# IHM.net
KiCad netlist of a schematic drawn in Altium Designer
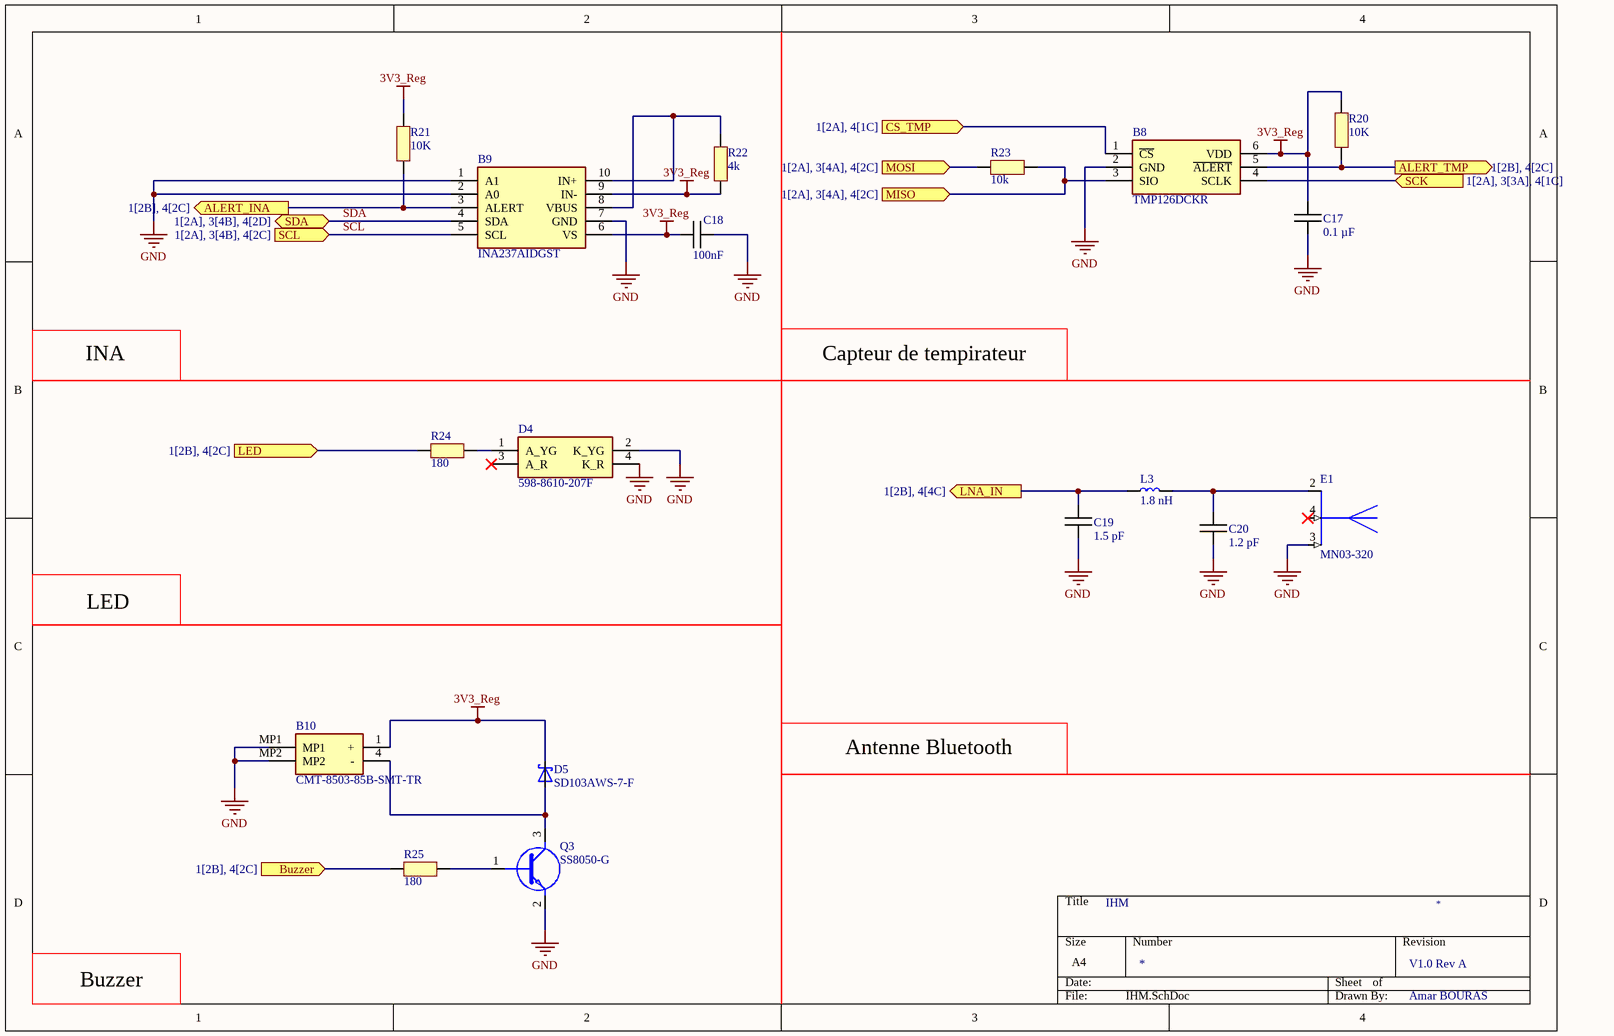
[diagram p0: IHM.SchDoc]

(export (version "E")
  (design (tool "Eeschema 10.0.6"))
  (components
    (comp (ref "B8")
      (value "TMP126DCKR")
      (footprint "SOT65P210X110-6N")
      (fields (field (name "MOUSER PART NUMBER") "595-TMP126DCKR"))
      (libsource (lib "SCHLibrary") (part "TMP126DCKR"))
    )
    (comp (ref "B9")
      (value "INA237AIDGST")
      (footprint "SOP50P490X110-10N")
      (fields (field (name "MOUSER PART NUMBER") "595-INA237AIDGST"))
      (libsource (lib "SCHLibrary") (part "INA237AIDGST"))
    )
    (comp (ref "B10")
      (value "CMT-8503-85B-SMT-TR")
      (footprint "CMT850385BSMTTR")
      (fields (field (name "MOUSER PART NUMBER") "490-CMT-850385BSMTTR"))
      (libsource (lib "SCHLibrary") (part "CMT-8503-85B-SMT-TR"))
    )
    (comp (ref "C17")
      (value "0.1 µF")
      (footprint "CAPC1005X06N")
      (libsource (lib "SCHLibrary") (part "Capacitor"))
    )
    (comp (ref "C18")
      (value "100nF")
      (footprint "CAPC1005X06N")
      (libsource (lib "SCHLibrary") (part "Capacitor"))
    )
    (comp (ref "C19")
      (value "1.5 pF")
      (footprint "CAPC1005X06N")
      (libsource (lib "SCHLibrary") (part "Capacitor"))
    )
    (comp (ref "C20")
      (value "1.2 pF")
      (footprint "CAPC1005X06N")
      (libsource (lib "SCHLibrary") (part "Capacitor"))
    )
    (comp (ref "D4")
      (value "598-8610-207F")
      (footprint "5988610207F")
      (description "Standard LEDs - SMD Red/Green WC 80/50mcd 645/570nm")
      (fields (field (name "MOUSER PART NUMBER") "645-598-8610-207F"))
      (libsource (lib "SCHLibrary") (part "598-8610-207F"))
    )
    (comp (ref "D5")
      (value "SD103AWS-7-F")
      (footprint "SD103AWS-7-F")
      (description "Diode Array 3 Independent Schottky 40V 175mA Surface Mount 6-TSSOP, SC-88, SOT-363")
      (libsource (lib "SCHLibrary") (part "SD103AWS-7-F"))
    )
    (comp (ref "E1")
      (value "MN03-320")
      (footprint "XCVR_NN03-320")
      (fields
        (field (name "MANUFACTURER_PART_NUMBER") "NN03-320")
        (field (name "MOUSER PART NUMBER") "128-NN03-320")
      )
      (libsource (lib "SCHLibrary") (part "NN03-320"))
    )
    (comp (ref "L3")
      (value "1.8 nH")
      (footprint "LQPC1005X06N")
      (libsource (lib "SCHLibrary") (part "Bobine"))
    )
    (comp (ref "Q3")
      (value "SS8050-G")
      (footprint "SS8050-G")
      (description "Bipolar Transistors - BJT NPN TRANSISTOR 1.5A 40V")
      (libsource (lib "SCHLibrary") (part "SS8050-G"))
    )
    (comp (ref "R20") (value "10K") (footprint "RESC1005X06N") (libsource (lib "") (part "Resistor_1")))
    (comp (ref "R21") (value "10K") (footprint "RESC1005X06N") (libsource (lib "") (part "Resistor_1")))
    (comp (ref "R22") (value "4k") (footprint "RESC1005X06N") (libsource (lib "") (part "Resistor_1")))
    (comp (ref "R23")
      (value "10k")
      (footprint "RESC1005X06N")
      (libsource (lib "SCHLibrary") (part "Resistor"))
    )
    (comp (ref "R24")
      (value "180")
      (footprint "RESC1005X06N")
      (libsource (lib "SCHLibrary") (part "Resistor"))
    )
    (comp (ref "R25")
      (value "180")
      (footprint "RESC1005X06N")
      (libsource (lib "SCHLibrary") (part "Resistor"))
    )
  )
  (nets
    (net (code "1") (name "/ALERT_INA") (class "Default")
      (node (ref "B9") (pin "3") (pinfunction "ALERT_3") (pintype "passive"))
      (node (ref "R21") (pin "1") (pinfunction "1_1") (pintype "passive"))
    )
    (net (code "2") (name "/ALERT_TMP") (class "Default")
      (node (ref "B8") (pin "5") (pinfunction "~{ALERT}_5") (pintype "passive"))
      (node (ref "R20") (pin "1") (pinfunction "1_1") (pintype "passive"))
    )
    (net (code "3") (name "/Buzzer") (class "Default")
      (node (ref "R25") (pin "2") (pinfunction "2_2") (pintype "passive"))
    )
    (net (code "4") (name "/CS_TMP") (class "Default")
      (node (ref "B8") (pin "1") (pinfunction "~{CS}_1") (pintype "passive"))
    )
    (net (code "5") (name "/LED") (class "Default")
      (node (ref "R24") (pin "2") (pinfunction "2_2") (pintype "passive"))
    )
    (net (code "6") (name "/LNA_IN") (class "Default")
      (node (ref "C19") (pin "2") (pinfunction "2_2") (pintype "passive"))
      (node (ref "L3") (pin "1") (pinfunction "1_1") (pintype "passive"))
    )
    (net (code "7") (name "/MISO") (class "Default")
      (node (ref "B8") (pin "3") (pinfunction "SIO_3") (pintype "passive"))
      (node (ref "R23") (pin "1") (pinfunction "1_1") (pintype "passive"))
    )
    (net (code "8") (name "/MOSI") (class "Default")
      (node (ref "R23") (pin "2") (pinfunction "2_2") (pintype "passive"))
    )
    (net (code "9") (name "/SCK") (class "Default")
      (node (ref "B8") (pin "4") (pinfunction "SCLK_4") (pintype "passive"))
    )
    (net (code "10") (name "/SCL") (class "Default")
      (node (ref "B9") (pin "5") (pinfunction "SCL_5") (pintype "passive"))
    )
    (net (code "11") (name "/SDA") (class "Default")
      (node (ref "B9") (pin "4") (pinfunction "SDA_4") (pintype "passive"))
    )
    (net (code "12") (name "3V3_Reg") (class "Default")
      (node (ref "B10") (pin "1") (pinfunction "+_1") (pintype "passive"))
      (node (ref "B8") (pin "6") (pinfunction "VDD_6") (pintype "passive"))
      (node (ref "B9") (pin "6") (pinfunction "VS_6") (pintype "passive"))
      (node (ref "B9") (pin "9") (pinfunction "IN-_9") (pintype "passive"))
      (node (ref "C17") (pin "2") (pinfunction "2_2") (pintype "passive"))
      (node (ref "C18") (pin "1") (pinfunction "1_1") (pintype "passive"))
      (node (ref "D5") (pin "1") (pinfunction "C_1") (pintype "passive"))
      (node (ref "R20") (pin "2") (pinfunction "2_2") (pintype "passive"))
      (node (ref "R21") (pin "2") (pinfunction "2_2") (pintype "passive"))
      (node (ref "R22") (pin "1") (pinfunction "1_1") (pintype "passive"))
    )
    (net (code "13") (name "GND") (class "Default")
      (node (ref "B10") (pin "MP1") (pinfunction "MP1_MP1") (pintype "passive"))
      (node (ref "B10") (pin "MP2") (pinfunction "MP2_MP2") (pintype "passive"))
      (node (ref "B8") (pin "2") (pinfunction "GND_2") (pintype "passive"))
      (node (ref "B9") (pin "1") (pinfunction "A1_1") (pintype "passive"))
      (node (ref "B9") (pin "2") (pinfunction "A0_2") (pintype "passive"))
      (node (ref "B9") (pin "7") (pinfunction "GND_7") (pintype "passive"))
      (node (ref "C17") (pin "1") (pinfunction "1_1") (pintype "passive"))
      (node (ref "C18") (pin "2") (pinfunction "2_2") (pintype "passive"))
      (node (ref "C19") (pin "1") (pinfunction "1_1") (pintype "passive"))
      (node (ref "C20") (pin "1") (pinfunction "1_1") (pintype "passive"))
      (node (ref "D4") (pin "2") (pinfunction "K_YG_2") (pintype "passive"))
      (node (ref "D4") (pin "4") (pinfunction "K_R_4") (pintype "passive"))
      (node (ref "E1") (pin "3") (pinfunction "FEED_BLUETOOTH_3") (pintype "input"))
      (node (ref "Q3") (pin "2") (pinfunction "E_2") (pintype "passive"))
    )
    (net (code "14") (name "Net-(B9-IN+)") (class "Default")
      (node (ref "B9") (pin "10") (pinfunction "IN+_10") (pintype "passive"))
      (node (ref "B9") (pin "8") (pinfunction "VBUS_8") (pintype "passive"))
      (node (ref "R22") (pin "2") (pinfunction "2_2") (pintype "passive"))
    )
    (net (code "15") (name "Net-(B10--)") (class "Default")
      (node (ref "B10") (pin "4") (pinfunction "-_4") (pintype "passive"))
      (node (ref "D5") (pin "2") (pinfunction "A_2") (pintype "passive"))
      (node (ref "Q3") (pin "3") (pinfunction "C_3") (pintype "passive"))
    )
    (net (code "16") (name "Net-(D4-A_YG)") (class "Default")
      (node (ref "D4") (pin "1") (pinfunction "A_YG_1") (pintype "passive"))
      (node (ref "R24") (pin "1") (pinfunction "1_1") (pintype "passive"))
    )
    (net (code "17") (name "Net-(E1-GROUND)") (class "Default")
      (node (ref "C20") (pin "2") (pinfunction "2_2") (pintype "passive"))
      (node (ref "E1") (pin "2") (pinfunction "GROUND_2") (pintype "power_in"))
      (node (ref "L3") (pin "2") (pinfunction "2_2") (pintype "passive"))
    )
    (net (code "18") (name "Net-(Q3-B)") (class "Default")
      (node (ref "Q3") (pin "1") (pinfunction "B_1") (pintype "passive"))
      (node (ref "R25") (pin "1") (pinfunction "1_1") (pintype "passive"))
    )
    (net (code "19") (name "unconnected-(D4-A_R-Pad3)") (class "Default")
      (node (ref "D4") (pin "3") (pinfunction "A_R_3") (pintype "passive+no_connect"))
    )
    (net (code "20") (name "unconnected-(E1-FEED_GNSS-Pad4)") (class "Default")
      (node (ref "E1") (pin "4") (pinfunction "FEED_GNSS_4") (pintype "input+no_connect"))
    )
  )
)
